# 2015PCB.net
KiCad netlist of a schematic drawn in Altium Designer
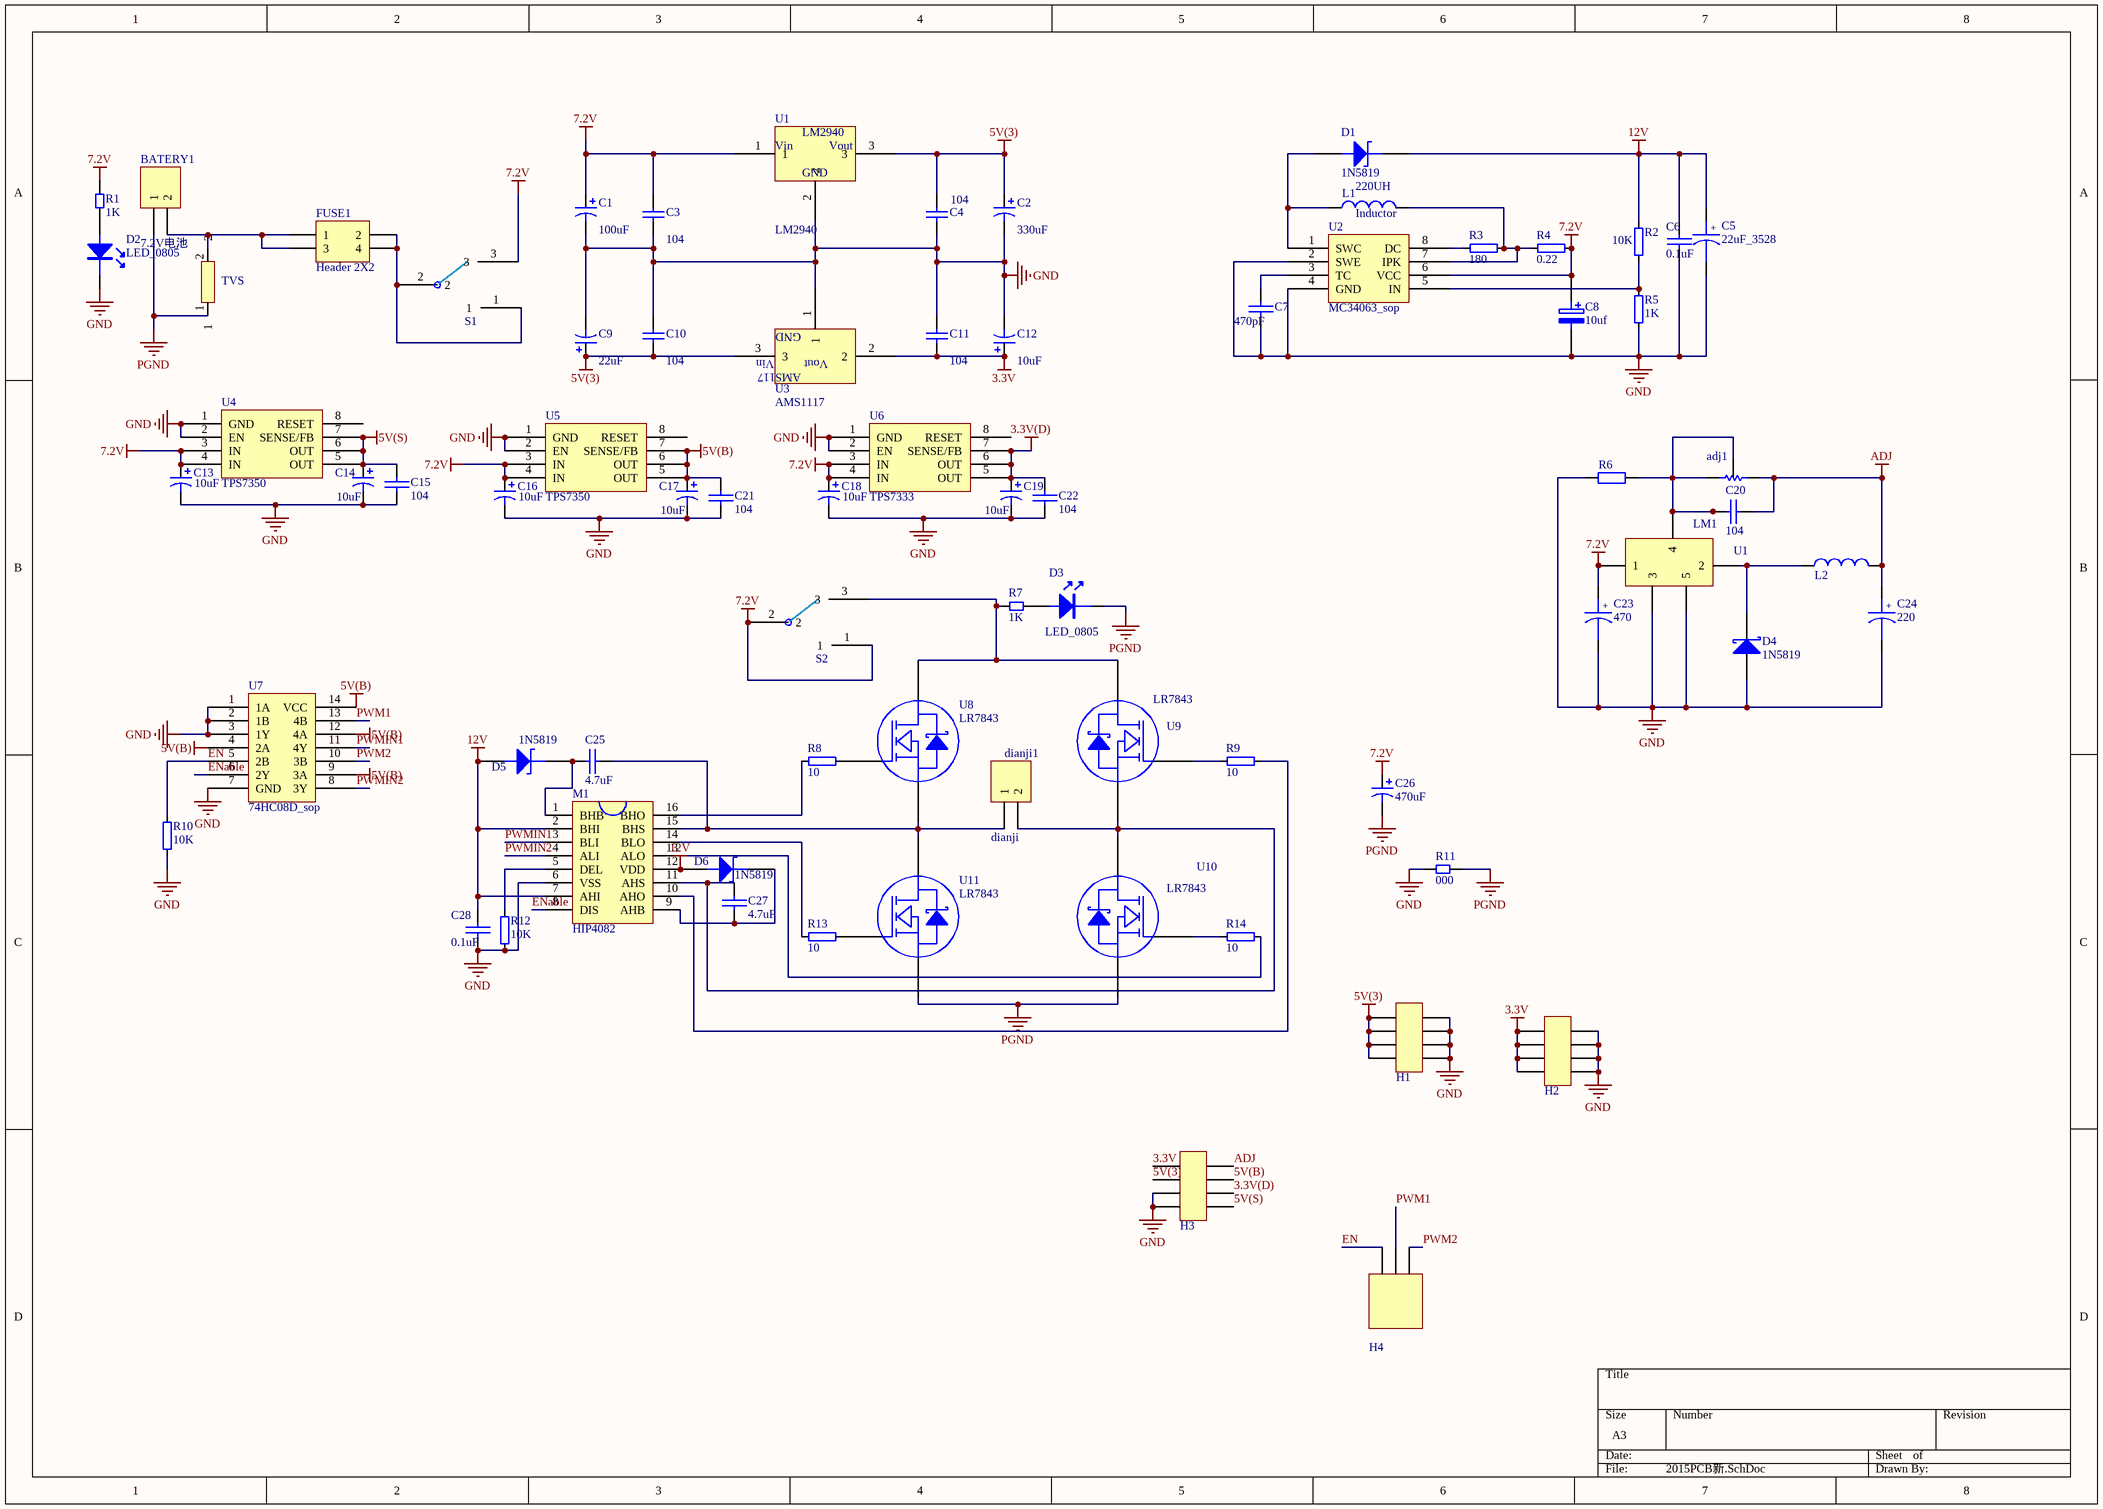
[diagram p0: 2015PCB新.SchDoc]

(export (version "E")
  (design (tool "Eeschema 10.0.6"))
  (components
    (comp (ref "adj1")
      (value "RISISTR_ADJ")
      (footprint "RISIATER_ADJ")
      (libsource (lib "gaoguang") (part "RISISTR_ADJ"))
    )
    (comp (ref "BATERY1")
      (value "7.2V电池")
      (footprint "source:PCBComponent_1")
      (description "Header, 2-Pin")
      (fields (field (name "PUBLISHER") "Altium Limited"))
      (libsource (lib "hongying") (part "Header 2"))
    )
    (comp (ref "C1")
      (value "100uF")
      (footprint "Cap(pol):PCBComponent_1")
      (description "Polarized Capacitor (Radial)")
      (fields (field (name "Comment") "Cap Pol1_1") (field (name "PUBLISHER") "Altium Limited"))
      (libsource (lib "hongying") (part "Cap Pol1_1"))
    )
    (comp (ref "C2")
      (value "330uF")
      (footprint "Cap(pol):PCBComponent_1")
      (description "Polarized Capacitor (Radial)")
      (fields (field (name "Comment") "Cap Pol1_1") (field (name "PUBLISHER") "Altium Limited"))
      (libsource (lib "hongying") (part "Cap Pol1_1"))
    )
    (comp (ref "C3")
      (value "104")
      (footprint "Cap:PCBComponent_1")
      (description "Capacitor")
      (fields (field (name "Comment") "Cap") (field (name "PUBLISHER") "Altium Limited"))
      (libsource (lib "hongying") (part "Cap"))
    )
    (comp (ref "C4")
      (value "104")
      (footprint "Cap:PCBComponent_1")
      (description "Capacitor")
      (fields (field (name "Comment") "Cap") (field (name "PUBLISHER") "Altium Limited"))
      (libsource (lib "hongying") (part "Cap"))
    )
    (comp (ref "C5")
      (value "22uF_3528")
      (footprint "3528_B")
      (libsource (lib "gyh的原理图库 ") (part "10uF_3528"))
    )
    (comp (ref "C6") (value "0.1uF") (footprint "0805") (libsource (lib "gyh的原理图库 ") (part "0.1uF_0805")))
    (comp (ref "C7") (value "470pF") (footprint "0805") (libsource (lib "gyh的原理图库 ") (part "0.1uF_0805")))
    (comp (ref "C8")
      (value "10uf")
      (footprint "1206")
      (description "Electrolytic Capacitor")
      (libsource (lib "Runner") (part "ELECTRO2_2"))
    )
    (comp (ref "C9")
      (value "22uF")
      (footprint "Cap(pol):PCBComponent_1")
      (description "Polarized Capacitor (Radial)")
      (fields (field (name "Comment") "Cap Pol1_1") (field (name "PUBLISHER") "Altium Limited"))
      (libsource (lib "hongying") (part "Cap Pol1_1"))
    )
    (comp (ref "C10")
      (value "104")
      (footprint "Cap:PCBComponent_1")
      (description "Capacitor")
      (fields (field (name "Comment") "Cap") (field (name "PUBLISHER") "Altium Limited"))
      (libsource (lib "hongying") (part "Cap"))
    )
    (comp (ref "C11")
      (value "104")
      (footprint "Cap:PCBComponent_1")
      (description "Capacitor")
      (fields (field (name "Comment") "Cap") (field (name "PUBLISHER") "Altium Limited"))
      (libsource (lib "hongying") (part "Cap"))
    )
    (comp (ref "C12")
      (value "10uF")
      (footprint "Cap(pol):PCBComponent_1")
      (description "Polarized Capacitor (Radial)")
      (fields (field (name "Comment") "Cap Pol1_1") (field (name "PUBLISHER") "Altium Limited"))
      (libsource (lib "hongying") (part "Cap Pol1_1"))
    )
    (comp (ref "C13")
      (value "10uF")
      (footprint "1206")
      (description "Polarized Capacitor (Radial)")
      (fields (field (name "PUBLISHER") "Altium Limited"))
      (libsource (lib "*") (part "Cap Pol1"))
    )
    (comp (ref "C14")
      (value "10uF")
      (footprint "1206")
      (description "Polarized Capacitor (Radial)")
      (fields (field (name "PUBLISHER") "Altium Limited"))
      (libsource (lib "*") (part "Cap Pol1"))
    )
    (comp (ref "C15")
      (value "104")
      (footprint "c0805")
      (description "Capacitor")
      (libsource (lib "*") (part "CAP"))
    )
    (comp (ref "C16")
      (value "10uF")
      (footprint "1206")
      (description "Polarized Capacitor (Radial)")
      (fields (field (name "PUBLISHER") "Altium Limited"))
      (libsource (lib "*") (part "Cap Pol1"))
    )
    (comp (ref "C17")
      (value "10uF")
      (footprint "1206")
      (description "Polarized Capacitor (Radial)")
      (fields (field (name "PUBLISHER") "Altium Limited"))
      (libsource (lib "*") (part "Cap Pol1"))
    )
    (comp (ref "C18")
      (value "10uF")
      (footprint "1206")
      (description "Polarized Capacitor (Radial)")
      (fields (field (name "PUBLISHER") "Altium Limited"))
      (libsource (lib "*") (part "Cap Pol1"))
    )
    (comp (ref "C19")
      (value "10uF")
      (footprint "1206")
      (description "Polarized Capacitor (Radial)")
      (fields (field (name "PUBLISHER") "Altium Limited"))
      (libsource (lib "*") (part "Cap Pol1"))
    )
    (comp (ref "C20")
      (value "104")
      (footprint "0805")
      (description "Capacitor")
      (libsource (lib "gaoguang") (part "CAP_1"))
    )
    (comp (ref "C21")
      (value "104")
      (footprint "c0805")
      (description "Capacitor")
      (libsource (lib "*") (part "CAP"))
    )
    (comp (ref "C22")
      (value "104")
      (footprint "c0805")
      (description "Capacitor")
      (libsource (lib "*") (part "CAP"))
    )
    (comp (ref "C23")
      (value "470")
      (footprint "Cap(pol):PCBComponent_1")
      (libsource (lib "gaoguang") (part "P_cap_C_100u"))
    )
    (comp (ref "C24")
      (value "220")
      (footprint "Cap(pol):PCBComponent_1")
      (libsource (lib "gaoguang") (part "P_cap_C_100u"))
    )
    (comp (ref "C25") (value "4.7uF") (footprint "0805") (libsource (lib "gyh的原理图库 ") (part "0.1uF_0805")))
    (comp (ref "C26")
      (value "470uF")
      (footprint "Cap(pol):PCBComponent_1")
      (description "Polarized Capacitor (Radial)")
      (fields (field (name "Comment") "Cap Pol1_1") (field (name "PUBLISHER") "Altium Limited"))
      (libsource (lib "hongying") (part "Cap Pol1_1"))
    )
    (comp (ref "C27") (value "4.7uF") (footprint "0805") (libsource (lib "gyh的原理图库 ") (part "0.1uF_0805")))
    (comp (ref "C28") (value "0.1uF") (footprint "0805") (libsource (lib "gyh的原理图库 ") (part "0.1uF_0805")))
    (comp (ref "D1")
      (value "1N5819")
      (footprint "SS14_SMA")
      (libsource (lib "gyh的原理图库 ") (part "1N5819_SMA"))
    )
    (comp (ref "D2") (value "LED_0805") (footprint "0805") (libsource (lib "gyh的原理图库 ") (part "LED_0805")))
    (comp (ref "D3") (value "LED_0805") (footprint "0805") (libsource (lib "gyh的原理图库 ") (part "LED_0805")))
    (comp (ref "D4") (value "1N5819") (footprint "1N5819") (libsource (lib "gaoguang") (part "1N5819")))
    (comp (ref "D5")
      (value "1N5819")
      (footprint "SS14_SMA")
      (libsource (lib "gyh的原理图库 ") (part "1N5819_SMA"))
    )
    (comp (ref "D6")
      (value "1N5819")
      (footprint "SS14_SMA")
      (libsource (lib "gyh的原理图库 ") (part "1N5819_SMA"))
    )
    (comp (ref "dianji1")
      (value "dianji")
      (footprint "source:PCBComponent_1")
      (description "Header, 2-Pin")
      (fields (field (name "PUBLISHER") "Altium Limited"))
      (libsource (lib "hongying") (part "Header 2"))
    )
    (comp (ref "erjiguan1") (value "TVS") (footprint "1812") (libsource (lib "TVS") (part "Component_1")))
    (comp (ref "FUSE1")
      (value "Header 2X2")
      (footprint "FUSE:PCBComponent_1")
      (description "Header, 2-Pin, Dual row")
      (fields (field (name "PUBLISHER") "Altium Limited"))
      (libsource (lib "hongying") (part "Header 2X2"))
    )
    (comp (ref "H1")
      (value "HEADER4X2")
      (footprint "HEADER4X2")
      (libsource (lib "Fu的原理图库") (part "HEADER4X2"))
    )
    (comp (ref "H2")
      (value "HEADER4X2")
      (footprint "HEADER4X2")
      (libsource (lib "Fu的原理图库") (part "HEADER4X2"))
    )
    (comp (ref "H3")
      (value "HEADER4X2")
      (footprint "HEADER4X2")
      (libsource (lib "Fu的原理图库") (part "HEADER4X2"))
    )
    (comp (ref "H4") (value "HEADER") (footprint "干簧管") (libsource (lib "Fu的原理图库") (part "HEADER3")))
    (comp (ref "L1")
      (value "Inductor")
      (footprint "L(pol):PCBComponent_1")
      (fields (field (name "ALTIUM_VALUE") "220UH") (field (name "PUBLISHER") "Altium Limited"))
      (libsource (lib "Runner") (part "Inductor"))
    )
    (comp (ref "L2") (value "L?") (footprint "7*7*4") (libsource (lib "gaoguang") (part "33Uinductor774")))
    (comp (ref "LM1") (value "U1") (footprint "LM2596") (libsource (lib "gaoguang") (part "LM2596")))
    (comp (ref "M1") (value "HIP4082") (footprint "SO-16") (libsource (lib "九届驱动电源") (part "HIP4082")))
    (comp (ref "R1")
      (value "1K")
      (footprint "0805")
      (fields (field (name "Comment") "RES"))
      (libsource (lib "Fu的原理图库") (part "0805-电阻"))
    )
    (comp (ref "R2") (value "10K") (footprint "0805") (libsource (lib "gyh的原理图库 ") (part "RES_0805")))
    (comp (ref "R3") (value "180") (footprint "0805") (libsource (lib "gyh的原理图库 ") (part "RES_0805")))
    (comp (ref "R4") (value "0.22") (footprint "0805") (libsource (lib "gyh的原理图库 ") (part "RES_0805")))
    (comp (ref "R5") (value "1K") (footprint "0805") (libsource (lib "gyh的原理图库 ") (part "RES_0805")))
    (comp (ref "R6")
      (value "Res2")
      (footprint "0805")
      (description "Resistor")
      (fields (field (name "PUBLISHER") "Altium Limited"))
      (libsource (lib "gaoguang") (part "Res2"))
    )
    (comp (ref "R7")
      (value "1K")
      (footprint "0805")
      (fields (field (name "Comment") "RES"))
      (libsource (lib "Fu的原理图库") (part "0805-电阻"))
    )
    (comp (ref "R8") (value "10") (footprint "0805") (libsource (lib "gyh的原理图库 ") (part "RES_0805")))
    (comp (ref "R9") (value "10") (footprint "0805") (libsource (lib "gyh的原理图库 ") (part "RES_0805")))
    (comp (ref "R10") (value "10K") (footprint "0805") (libsource (lib "gyh的原理图库 ") (part "RES_0805")))
    (comp (ref "R11")
      (value "000")
      (footprint "0805")
      (fields (field (name "Comment") "RES"))
      (libsource (lib "Fu的原理图库") (part "0805-电阻"))
    )
    (comp (ref "R12") (value "10K") (footprint "0805") (libsource (lib "gyh的原理图库 ") (part "RES_0805")))
    (comp (ref "R13") (value "10") (footprint "0805") (libsource (lib "gyh的原理图库 ") (part "RES_0805")))
    (comp (ref "R14") (value "10") (footprint "0805") (libsource (lib "gyh的原理图库 ") (part "RES_0805")))
    (comp (ref "S1")
      (value "单刀双掷开关")
      (footprint "Fu的元件封装库:三脚开关")
      (libsource (lib "hongying") (part "单刀双掷开关"))
    )
    (comp (ref "S2")
      (value "单刀双掷开关")
      (footprint "Fu的元件封装库:三脚开关")
      (libsource (lib "hongying") (part "单刀双掷开关"))
    )
    (comp (ref "U1")
      (value "LM2940")
      (footprint "DIP2_2:PCBComponent_1")
      (libsource (lib "hongying") (part "LM2940"))
    )
    (comp (ref "U2")
      (value "MC34063_sop")
      (footprint "SOP-8")
      (libsource (lib "gyh的原理图库 ") (part "MC34063_sop"))
    )
    (comp (ref "U3")
      (value "AMS1117")
      (footprint "SOT223_forAMS1117")
      (libsource (lib "hongying") (part "AMS1117"))
    )
    (comp (ref "U4") (value "TPS7350") (footprint "SO-8") (libsource (lib "*") (part "TPS7350")))
    (comp (ref "U5") (value "TPS7350") (footprint "SO-8") (libsource (lib "*") (part "TPS7350")))
    (comp (ref "U6") (value "TPS7333") (footprint "SO-8") (libsource (lib "*") (part "TPS7350")))
    (comp (ref "U7")
      (value "74HC08D_sop")
      (footprint "SOP-14")
      (libsource (lib "gyh的原理图库 ") (part "74HCT00D_sop"))
    )
    (comp (ref "U8") (value "LR7843") (footprint "DPAK") (libsource (lib "gyh的原理图库 ") (part "IRF3205_D2PAK")))
    (comp (ref "U9") (value "LR7843") (footprint "DPAK") (libsource (lib "gyh的原理图库 ") (part "IRF3205_D2PAK")))
    (comp (ref "U10")
      (value "LR7843")
      (footprint "DPAK")
      (libsource (lib "gyh的原理图库 ") (part "IRF3205_D2PAK"))
    )
    (comp (ref "U11")
      (value "LR7843")
      (footprint "DPAK")
      (libsource (lib "gyh的原理图库 ") (part "IRF3205_D2PAK"))
    )
  )
  (nets
    (net (code "1") (name "/EN") (class "Default")
      (node (ref "H4") (pin "3") (pinfunction "3_3") (pintype "passive"))
      (node (ref "R10") (pin "2") (pinfunction "2_2") (pintype "passive"))
      (node (ref "U7") (pin "5") (pinfunction "2B_5") (pintype "passive"))
    )
    (net (code "2") (name "/ENable") (class "Default")
      (node (ref "M1") (pin "8") (pinfunction "DIS_8") (pintype "passive"))
      (node (ref "U7") (pin "6") (pinfunction "2Y_6") (pintype "passive"))
    )
    (net (code "3") (name "/PWM1") (class "Default")
      (node (ref "H4") (pin "2") (pinfunction "2_2") (pintype "passive"))
      (node (ref "U7") (pin "13") (pinfunction "4B_13") (pintype "passive"))
    )
    (net (code "4") (name "/PWM2") (class "Default")
      (node (ref "H4") (pin "1") (pinfunction "1_1") (pintype "passive"))
      (node (ref "U7") (pin "10") (pinfunction "3B_10") (pintype "passive"))
    )
    (net (code "5") (name "/PWMIN1") (class "Default")
      (node (ref "M1") (pin "3") (pinfunction "BLI_3") (pintype "passive"))
      (node (ref "U7") (pin "11") (pinfunction "4Y_11") (pintype "passive"))
    )
    (net (code "6") (name "/PWMIN2") (class "Default")
      (node (ref "M1") (pin "4") (pinfunction "ALI_4") (pintype "passive"))
      (node (ref "U7") (pin "8") (pinfunction "3Y_8") (pintype "passive"))
    )
    (net (code "7") (name "3.3V") (class "Default")
      (node (ref "C11") (pin "1") (pinfunction "1_1") (pintype "passive"))
      (node (ref "C12") (pin "1") (pinfunction "1_1") (pintype "passive"))
      (node (ref "H2") (pin "1") (pinfunction "1_1") (pintype "passive"))
      (node (ref "H2") (pin "2") (pinfunction "2_2") (pintype "passive"))
      (node (ref "H2") (pin "3") (pinfunction "3_3") (pintype "passive"))
      (node (ref "H2") (pin "4") (pinfunction "4_4") (pintype "passive"))
      (node (ref "H3") (pin "1") (pinfunction "1_1") (pintype "passive"))
      (node (ref "U3") (pin "2") (pinfunction "2_2") (pintype "passive"))
    )
    (net (code "8") (name "3.3V(D)") (class "Default")
      (node (ref "C19") (pin "1") (pinfunction "1_1") (pintype "passive"))
      (node (ref "C22") (pin "1") (pinfunction "1_1") (pintype "passive"))
      (node (ref "H3") (pin "6") (pinfunction "6_6") (pintype "passive"))
      (node (ref "U6") (pin "5") (pinfunction "OUT_5") (pintype "passive"))
      (node (ref "U6") (pin "6") (pinfunction "OUT_6") (pintype "passive"))
      (node (ref "U6") (pin "7") (pinfunction "SENSE/FB_7") (pintype "passive"))
    )
    (net (code "9") (name "5V(3)") (class "Default")
      (node (ref "C10") (pin "1") (pinfunction "1_1") (pintype "passive"))
      (node (ref "C2") (pin "1") (pinfunction "1_1") (pintype "passive"))
      (node (ref "C4") (pin "2") (pinfunction "2_2") (pintype "passive"))
      (node (ref "C9") (pin "1") (pinfunction "1_1") (pintype "passive"))
      (node (ref "H1") (pin "1") (pinfunction "1_1") (pintype "passive"))
      (node (ref "H1") (pin "2") (pinfunction "2_2") (pintype "passive"))
      (node (ref "H1") (pin "3") (pinfunction "3_3") (pintype "passive"))
      (node (ref "H1") (pin "4") (pinfunction "4_4") (pintype "passive"))
      (node (ref "H3") (pin "2") (pinfunction "2_2") (pintype "passive"))
      (node (ref "U1") (pin "3") (pinfunction "3_3") (pintype "passive"))
      (node (ref "U3") (pin "3") (pinfunction "3_3") (pintype "passive"))
    )
    (net (code "10") (name "5V(B)") (class "Default")
      (node (ref "C17") (pin "1") (pinfunction "1_1") (pintype "passive"))
      (node (ref "C21") (pin "1") (pinfunction "1_1") (pintype "passive"))
      (node (ref "H3") (pin "7") (pinfunction "7_7") (pintype "passive"))
      (node (ref "U5") (pin "5") (pinfunction "OUT_5") (pintype "passive"))
      (node (ref "U5") (pin "6") (pinfunction "OUT_6") (pintype "passive"))
      (node (ref "U5") (pin "7") (pinfunction "SENSE/FB_7") (pintype "passive"))
      (node (ref "U7") (pin "12") (pinfunction "4A_12") (pintype "passive"))
      (node (ref "U7") (pin "14") (pinfunction "VCC_14") (pintype "passive"))
      (node (ref "U7") (pin "4") (pinfunction "2A_4") (pintype "passive"))
      (node (ref "U7") (pin "9") (pinfunction "3A_9") (pintype "passive"))
    )
    (net (code "11") (name "5V(S)") (class "Default")
      (node (ref "C14") (pin "1") (pinfunction "1_1") (pintype "passive"))
      (node (ref "C15") (pin "1") (pinfunction "1_1") (pintype "passive"))
      (node (ref "H3") (pin "5") (pinfunction "5_5") (pintype "passive"))
      (node (ref "U4") (pin "5") (pinfunction "OUT_5") (pintype "passive"))
      (node (ref "U4") (pin "6") (pinfunction "OUT_6") (pintype "passive"))
      (node (ref "U4") (pin "7") (pinfunction "SENSE/FB_7") (pintype "passive"))
    )
    (net (code "12") (name "7.2V") (class "Default")
      (node (ref "C1") (pin "1") (pinfunction "1_1") (pintype "passive"))
      (node (ref "C13") (pin "1") (pinfunction "1_1") (pintype "passive"))
      (node (ref "C16") (pin "1") (pinfunction "1_1") (pintype "passive"))
      (node (ref "C18") (pin "1") (pinfunction "1_1") (pintype "passive"))
      (node (ref "C23") (pin "1") (pinfunction "1_1") (pintype "passive"))
      (node (ref "C26") (pin "1") (pinfunction "1_1") (pintype "passive"))
      (node (ref "C3") (pin "2") (pinfunction "2_2") (pintype "passive"))
      (node (ref "C8") (pin "1") (pinfunction "1_1") (pintype "passive"))
      (node (ref "LM1") (pin "1") (pinfunction "1_1") (pintype "passive"))
      (node (ref "R1") (pin "1") (pinfunction "1_1") (pintype "passive"))
      (node (ref "R4") (pin "2") (pinfunction "2_2") (pintype "passive"))
      (node (ref "S1") (pin "3") (pinfunction "3_3") (pintype "passive"))
      (node (ref "S2") (pin "1") (pinfunction "1_1") (pintype "passive"))
      (node (ref "S2") (pin "2") (pinfunction "2_2") (pintype "passive"))
      (node (ref "U1") (pin "1") (pinfunction "1_1") (pintype "passive"))
      (node (ref "U2") (pin "6") (pinfunction "VCC_6") (pintype "passive"))
      (node (ref "U4") (pin "3") (pinfunction "IN_3") (pintype "passive"))
      (node (ref "U4") (pin "4") (pinfunction "IN_4") (pintype "passive"))
      (node (ref "U5") (pin "3") (pinfunction "IN_3") (pintype "passive"))
      (node (ref "U5") (pin "4") (pinfunction "IN_4") (pintype "passive"))
      (node (ref "U6") (pin "3") (pinfunction "IN_3") (pintype "passive"))
      (node (ref "U6") (pin "4") (pinfunction "IN_4") (pintype "passive"))
    )
    (net (code "13") (name "12V") (class "Default")
      (node (ref "C28") (pin "1") (pinfunction "1_1") (pintype "passive"))
      (node (ref "C5") (pin "1") (pinfunction "1_1") (pintype "passive"))
      (node (ref "C6") (pin "1") (pinfunction "1_1") (pintype "passive"))
      (node (ref "D1") (pin "2") (pinfunction "K_2") (pintype "passive"))
      (node (ref "D5") (pin "1") (pinfunction "A_1") (pintype "passive"))
      (node (ref "D6") (pin "1") (pinfunction "A_1") (pintype "passive"))
      (node (ref "M1") (pin "12") (pinfunction "VDD_12") (pintype "passive"))
      (node (ref "M1") (pin "2") (pinfunction "BHI_2") (pintype "passive"))
      (node (ref "M1") (pin "7") (pinfunction "AHI_7") (pintype "passive"))
      (node (ref "R2") (pin "1") (pinfunction "1_1") (pintype "passive"))
    )
    (net (code "14") (name "ADJ") (class "Default")
      (node (ref "C20") (pin "2") (pinfunction "2_2") (pintype "passive"))
      (node (ref "C24") (pin "1") (pinfunction "1_1") (pintype "passive"))
      (node (ref "H3") (pin "8") (pinfunction "8_8") (pintype "passive"))
      (node (ref "L2") (pin "2") (pinfunction "2_2") (pintype "passive"))
      (node (ref "adj1") (pin "3") (pinfunction "3_3") (pintype "passive"))
    )
    (net (code "15") (name "GND") (class "Default")
      (node (ref "C1") (pin "2") (pinfunction "2_2") (pintype "passive"))
      (node (ref "C10") (pin "2") (pinfunction "2_2") (pintype "passive"))
      (node (ref "C11") (pin "2") (pinfunction "2_2") (pintype "passive"))
      (node (ref "C12") (pin "2") (pinfunction "2_2") (pintype "passive"))
      (node (ref "C13") (pin "2") (pinfunction "2_2") (pintype "passive"))
      (node (ref "C14") (pin "2") (pinfunction "2_2") (pintype "passive"))
      (node (ref "C15") (pin "2") (pinfunction "2_2") (pintype "passive"))
      (node (ref "C16") (pin "2") (pinfunction "2_2") (pintype "passive"))
      (node (ref "C17") (pin "2") (pinfunction "2_2") (pintype "passive"))
      (node (ref "C18") (pin "2") (pinfunction "2_2") (pintype "passive"))
      (node (ref "C19") (pin "2") (pinfunction "2_2") (pintype "passive"))
      (node (ref "C2") (pin "2") (pinfunction "2_2") (pintype "passive"))
      (node (ref "C21") (pin "2") (pinfunction "2_2") (pintype "passive"))
      (node (ref "C22") (pin "2") (pinfunction "2_2") (pintype "passive"))
      (node (ref "C23") (pin "2") (pinfunction "2_2") (pintype "passive"))
      (node (ref "C24") (pin "2") (pinfunction "2_2") (pintype "passive"))
      (node (ref "C28") (pin "2") (pinfunction "2_2") (pintype "passive"))
      (node (ref "C3") (pin "1") (pinfunction "1_1") (pintype "passive"))
      (node (ref "C4") (pin "1") (pinfunction "1_1") (pintype "passive"))
      (node (ref "C5") (pin "2") (pinfunction "2_2") (pintype "passive"))
      (node (ref "C6") (pin "2") (pinfunction "2_2") (pintype "passive"))
      (node (ref "C7") (pin "2") (pinfunction "2_2") (pintype "passive"))
      (node (ref "C8") (pin "2") (pinfunction "2_2") (pintype "passive"))
      (node (ref "C9") (pin "2") (pinfunction "2_2") (pintype "passive"))
      (node (ref "D2") (pin "2") (pinfunction "2_2") (pintype "passive"))
      (node (ref "D4") (pin "1") (pinfunction "1_1") (pintype "passive"))
      (node (ref "H1") (pin "5") (pinfunction "5_5") (pintype "passive"))
      (node (ref "H1") (pin "6") (pinfunction "6_6") (pintype "passive"))
      (node (ref "H1") (pin "7") (pinfunction "7_7") (pintype "passive"))
      (node (ref "H1") (pin "8") (pinfunction "8_8") (pintype "passive"))
      (node (ref "H2") (pin "5") (pinfunction "5_5") (pintype "passive"))
      (node (ref "H2") (pin "6") (pinfunction "6_6") (pintype "passive"))
      (node (ref "H2") (pin "7") (pinfunction "7_7") (pintype "passive"))
      (node (ref "H2") (pin "8") (pinfunction "8_8") (pintype "passive"))
      (node (ref "H3") (pin "3") (pinfunction "3_3") (pintype "passive"))
      (node (ref "H3") (pin "4") (pinfunction "4_4") (pintype "passive"))
      (node (ref "LM1") (pin "3") (pinfunction "3_3") (pintype "passive"))
      (node (ref "LM1") (pin "5") (pinfunction "5_5") (pintype "passive"))
      (node (ref "M1") (pin "6") (pinfunction "VSS_6") (pintype "passive"))
      (node (ref "R10") (pin "1") (pinfunction "1_1") (pintype "passive"))
      (node (ref "R11") (pin "1") (pinfunction "1_1") (pintype "passive"))
      (node (ref "R12") (pin "1") (pinfunction "1_1") (pintype "passive"))
      (node (ref "R5") (pin "1") (pinfunction "1_1") (pintype "passive"))
      (node (ref "R6") (pin "1") (pinfunction "1_1") (pintype "passive"))
      (node (ref "U1") (pin "2") (pinfunction "2_2") (pintype "passive"))
      (node (ref "U2") (pin "2") (pinfunction "SWE_2") (pintype "passive"))
      (node (ref "U2") (pin "4") (pinfunction "GND_4") (pintype "passive"))
      (node (ref "U3") (pin "1") (pinfunction "1_1") (pintype "passive"))
      (node (ref "U4") (pin "1") (pinfunction "GND_1") (pintype "passive"))
      (node (ref "U4") (pin "2") (pinfunction "EN_2") (pintype "passive"))
      (node (ref "U5") (pin "1") (pinfunction "GND_1") (pintype "passive"))
      (node (ref "U5") (pin "2") (pinfunction "EN_2") (pintype "passive"))
      (node (ref "U6") (pin "1") (pinfunction "GND_1") (pintype "passive"))
      (node (ref "U6") (pin "2") (pinfunction "EN_2") (pintype "passive"))
      (node (ref "U7") (pin "1") (pinfunction "1A_1") (pintype "passive"))
      (node (ref "U7") (pin "2") (pinfunction "1B_2") (pintype "passive"))
      (node (ref "U7") (pin "3") (pinfunction "1Y_3") (pintype "passive"))
      (node (ref "U7") (pin "7") (pinfunction "GND_7") (pintype "passive"))
    )
    (net (code "16") (name "Net-(BATERY1-Pad2)") (class "Default")
      (node (ref "BATERY1") (pin "2") (pinfunction "2_2") (pintype "passive"))
      (node (ref "FUSE1") (pin "1") (pinfunction "1_1") (pintype "passive"))
      (node (ref "FUSE1") (pin "3") (pinfunction "3_3") (pintype "passive"))
    )
    (net (code "17") (name "Net-(C20-Pad1)") (class "Default")
      (node (ref "C20") (pin "1") (pinfunction "1_1") (pintype "passive"))
      (node (ref "LM1") (pin "4") (pinfunction "4_4") (pintype "passive"))
      (node (ref "R6") (pin "2") (pinfunction "2_2") (pintype "passive"))
      (node (ref "adj1") (pin "1") (pinfunction "1_1") (pintype "passive"))
      (node (ref "adj1") (pin "2") (pinfunction "2_2") (pintype "passive"))
    )
    (net (code "18") (name "Net-(D1-A)") (class "Default")
      (node (ref "D1") (pin "1") (pinfunction "A_1") (pintype "passive"))
      (node (ref "L1") (pin "1") (pinfunction "1_1") (pintype "passive"))
      (node (ref "U2") (pin "1") (pinfunction "SWC_1") (pintype "passive"))
    )
    (net (code "19") (name "Net-(D2-Pad1)") (class "Default")
      (node (ref "D2") (pin "1") (pinfunction "1_1") (pintype "passive"))
      (node (ref "R1") (pin "2") (pinfunction "2_2") (pintype "passive"))
    )
    (net (code "20") (name "Net-(D3-Pad1)") (class "Default")
      (node (ref "D3") (pin "1") (pinfunction "1_1") (pintype "passive"))
      (node (ref "R7") (pin "2") (pinfunction "2_2") (pintype "passive"))
    )
    (net (code "21") (name "Net-(D4-Pad2)") (class "Default")
      (node (ref "D4") (pin "2") (pinfunction "2_2") (pintype "passive"))
      (node (ref "L2") (pin "1") (pinfunction "1_1") (pintype "passive"))
      (node (ref "LM1") (pin "2") (pinfunction "2_2") (pintype "passive"))
    )
    (net (code "22") (name "Net-(D5-K)") (class "Default")
      (node (ref "C25") (pin "2") (pinfunction "2_2") (pintype "passive"))
      (node (ref "D5") (pin "2") (pinfunction "K_2") (pintype "passive"))
      (node (ref "M1") (pin "1") (pinfunction "BHB_1") (pintype "passive"))
    )
    (net (code "23") (name "Net-(D6-K)") (class "Default")
      (node (ref "C27") (pin "2") (pinfunction "2_2") (pintype "passive"))
      (node (ref "D6") (pin "2") (pinfunction "K_2") (pintype "passive"))
      (node (ref "M1") (pin "9") (pinfunction "AHB_9") (pintype "passive"))
    )
    (net (code "24") (name "Net-(FUSE1-Pad2)") (class "Default")
      (node (ref "FUSE1") (pin "2") (pinfunction "2_2") (pintype "passive"))
      (node (ref "FUSE1") (pin "4") (pinfunction "4_4") (pintype "passive"))
      (node (ref "S1") (pin "1") (pinfunction "1_1") (pintype "passive"))
      (node (ref "S1") (pin "2") (pinfunction "2_2") (pintype "passive"))
    )
    (net (code "25") (name "Net-(M1-AHO)") (class "Default")
      (node (ref "M1") (pin "10") (pinfunction "AHO_10") (pintype "passive"))
      (node (ref "R9") (pin "2") (pinfunction "2_2") (pintype "passive"))
    )
    (net (code "26") (name "Net-(M1-AHS)") (class "Default")
      (node (ref "C27") (pin "1") (pinfunction "1_1") (pintype "passive"))
      (node (ref "M1") (pin "11") (pinfunction "AHS_11") (pintype "passive"))
      (node (ref "U10") (pin "2") (pinfunction "D_2") (pintype "passive"))
      (node (ref "U9") (pin "3") (pinfunction "S_3") (pintype "passive"))
      (node (ref "dianji1") (pin "2") (pinfunction "2_2") (pintype "passive"))
    )
    (net (code "27") (name "Net-(M1-ALO)") (class "Default")
      (node (ref "M1") (pin "13") (pinfunction "ALO_13") (pintype "passive"))
      (node (ref "R14") (pin "2") (pinfunction "2_2") (pintype "passive"))
    )
    (net (code "28") (name "Net-(M1-BHO)") (class "Default")
      (node (ref "M1") (pin "16") (pinfunction "BHO_16") (pintype "passive"))
      (node (ref "R8") (pin "1") (pinfunction "1_1") (pintype "passive"))
    )
    (net (code "29") (name "Net-(M1-BHS)") (class "Default")
      (node (ref "C25") (pin "1") (pinfunction "1_1") (pintype "passive"))
      (node (ref "M1") (pin "15") (pinfunction "BHS_15") (pintype "passive"))
      (node (ref "U11") (pin "2") (pinfunction "D_2") (pintype "passive"))
      (node (ref "U8") (pin "3") (pinfunction "S_3") (pintype "passive"))
      (node (ref "dianji1") (pin "1") (pinfunction "1_1") (pintype "passive"))
    )
    (net (code "30") (name "Net-(M1-BLO)") (class "Default")
      (node (ref "M1") (pin "14") (pinfunction "BLO_14") (pintype "passive"))
      (node (ref "R13") (pin "1") (pinfunction "1_1") (pintype "passive"))
    )
    (net (code "31") (name "Net-(M1-DEL)") (class "Default")
      (node (ref "M1") (pin "5") (pinfunction "DEL_5") (pintype "passive"))
      (node (ref "R12") (pin "2") (pinfunction "2_2") (pintype "passive"))
    )
    (net (code "32") (name "Net-(U2-DC)") (class "Default")
      (node (ref "R3") (pin "1") (pinfunction "1_1") (pintype "passive"))
      (node (ref "U2") (pin "8") (pinfunction "DC_8") (pintype "passive"))
    )
    (net (code "33") (name "Net-(U2-IN)") (class "Default")
      (node (ref "R2") (pin "2") (pinfunction "2_2") (pintype "passive"))
      (node (ref "R5") (pin "2") (pinfunction "2_2") (pintype "passive"))
      (node (ref "U2") (pin "5") (pinfunction "IN_5") (pintype "passive"))
    )
    (net (code "34") (name "Net-(U2-IPK)") (class "Default")
      (node (ref "L1") (pin "2") (pinfunction "2_2") (pintype "passive"))
      (node (ref "R3") (pin "2") (pinfunction "2_2") (pintype "passive"))
      (node (ref "R4") (pin "1") (pinfunction "1_1") (pintype "passive"))
      (node (ref "U2") (pin "7") (pinfunction "IPK_7") (pintype "passive"))
    )
    (net (code "35") (name "Net-(U2-TC)") (class "Default")
      (node (ref "C7") (pin "1") (pinfunction "1_1") (pintype "passive"))
      (node (ref "U2") (pin "3") (pinfunction "TC_3") (pintype "passive"))
    )
    (net (code "36") (name "Net-(U8-D)") (class "Default")
      (node (ref "R7") (pin "1") (pinfunction "1_1") (pintype "passive"))
      (node (ref "S2") (pin "3") (pinfunction "3_3") (pintype "passive"))
      (node (ref "U8") (pin "2") (pinfunction "D_2") (pintype "passive"))
      (node (ref "U9") (pin "2") (pinfunction "D_2") (pintype "passive"))
    )
    (net (code "37") (name "Net-(U8-G)") (class "Default")
      (node (ref "R8") (pin "2") (pinfunction "2_2") (pintype "passive"))
      (node (ref "U8") (pin "1") (pinfunction "G_1") (pintype "passive"))
    )
    (net (code "38") (name "Net-(U9-G)") (class "Default")
      (node (ref "R9") (pin "1") (pinfunction "1_1") (pintype "passive"))
      (node (ref "U9") (pin "1") (pinfunction "G_1") (pintype "passive"))
    )
    (net (code "39") (name "Net-(U10-G)") (class "Default")
      (node (ref "R14") (pin "1") (pinfunction "1_1") (pintype "passive"))
      (node (ref "U10") (pin "1") (pinfunction "G_1") (pintype "passive"))
    )
    (net (code "40") (name "Net-(U11-G)") (class "Default")
      (node (ref "R13") (pin "2") (pinfunction "2_2") (pintype "passive"))
      (node (ref "U11") (pin "1") (pinfunction "G_1") (pintype "passive"))
    )
    (net (code "41") (name "PGND") (class "Default")
      (node (ref "BATERY1") (pin "1") (pinfunction "1_1") (pintype "passive"))
      (node (ref "C26") (pin "2") (pinfunction "2_2") (pintype "passive"))
      (node (ref "D3") (pin "2") (pinfunction "2_2") (pintype "passive"))
      (node (ref "R11") (pin "2") (pinfunction "2_2") (pintype "passive"))
      (node (ref "U10") (pin "3") (pinfunction "S_3") (pintype "passive"))
      (node (ref "U11") (pin "3") (pinfunction "S_3") (pintype "passive"))
    )
    (net (code "42") (name "unconnected-(U4-RESET-Pad8)") (class "Default")
      (node (ref "U4") (pin "8") (pinfunction "RESET_8") (pintype "passive"))
    )
    (net (code "43") (name "unconnected-(U5-RESET-Pad8)") (class "Default")
      (node (ref "U5") (pin "8") (pinfunction "RESET_8") (pintype "passive"))
    )
    (net (code "44") (name "unconnected-(U6-RESET-Pad8)") (class "Default")
      (node (ref "U6") (pin "8") (pinfunction "RESET_8") (pintype "passive"))
    )
    (net (code "45") (name "unconnected-(erjiguan1-Pad1)") (class "Default")
      (node (ref "erjiguan1") (pin "1") (pinfunction "1_1") (pintype "passive"))
    )
    (net (code "46") (name "unconnected-(erjiguan1-Pad2)") (class "Default")
      (node (ref "erjiguan1") (pin "2") (pinfunction "2_2") (pintype "passive"))
    )
  )
)
